# mb_01.net
KiCad netlist of a schematic drawn in EAGLE
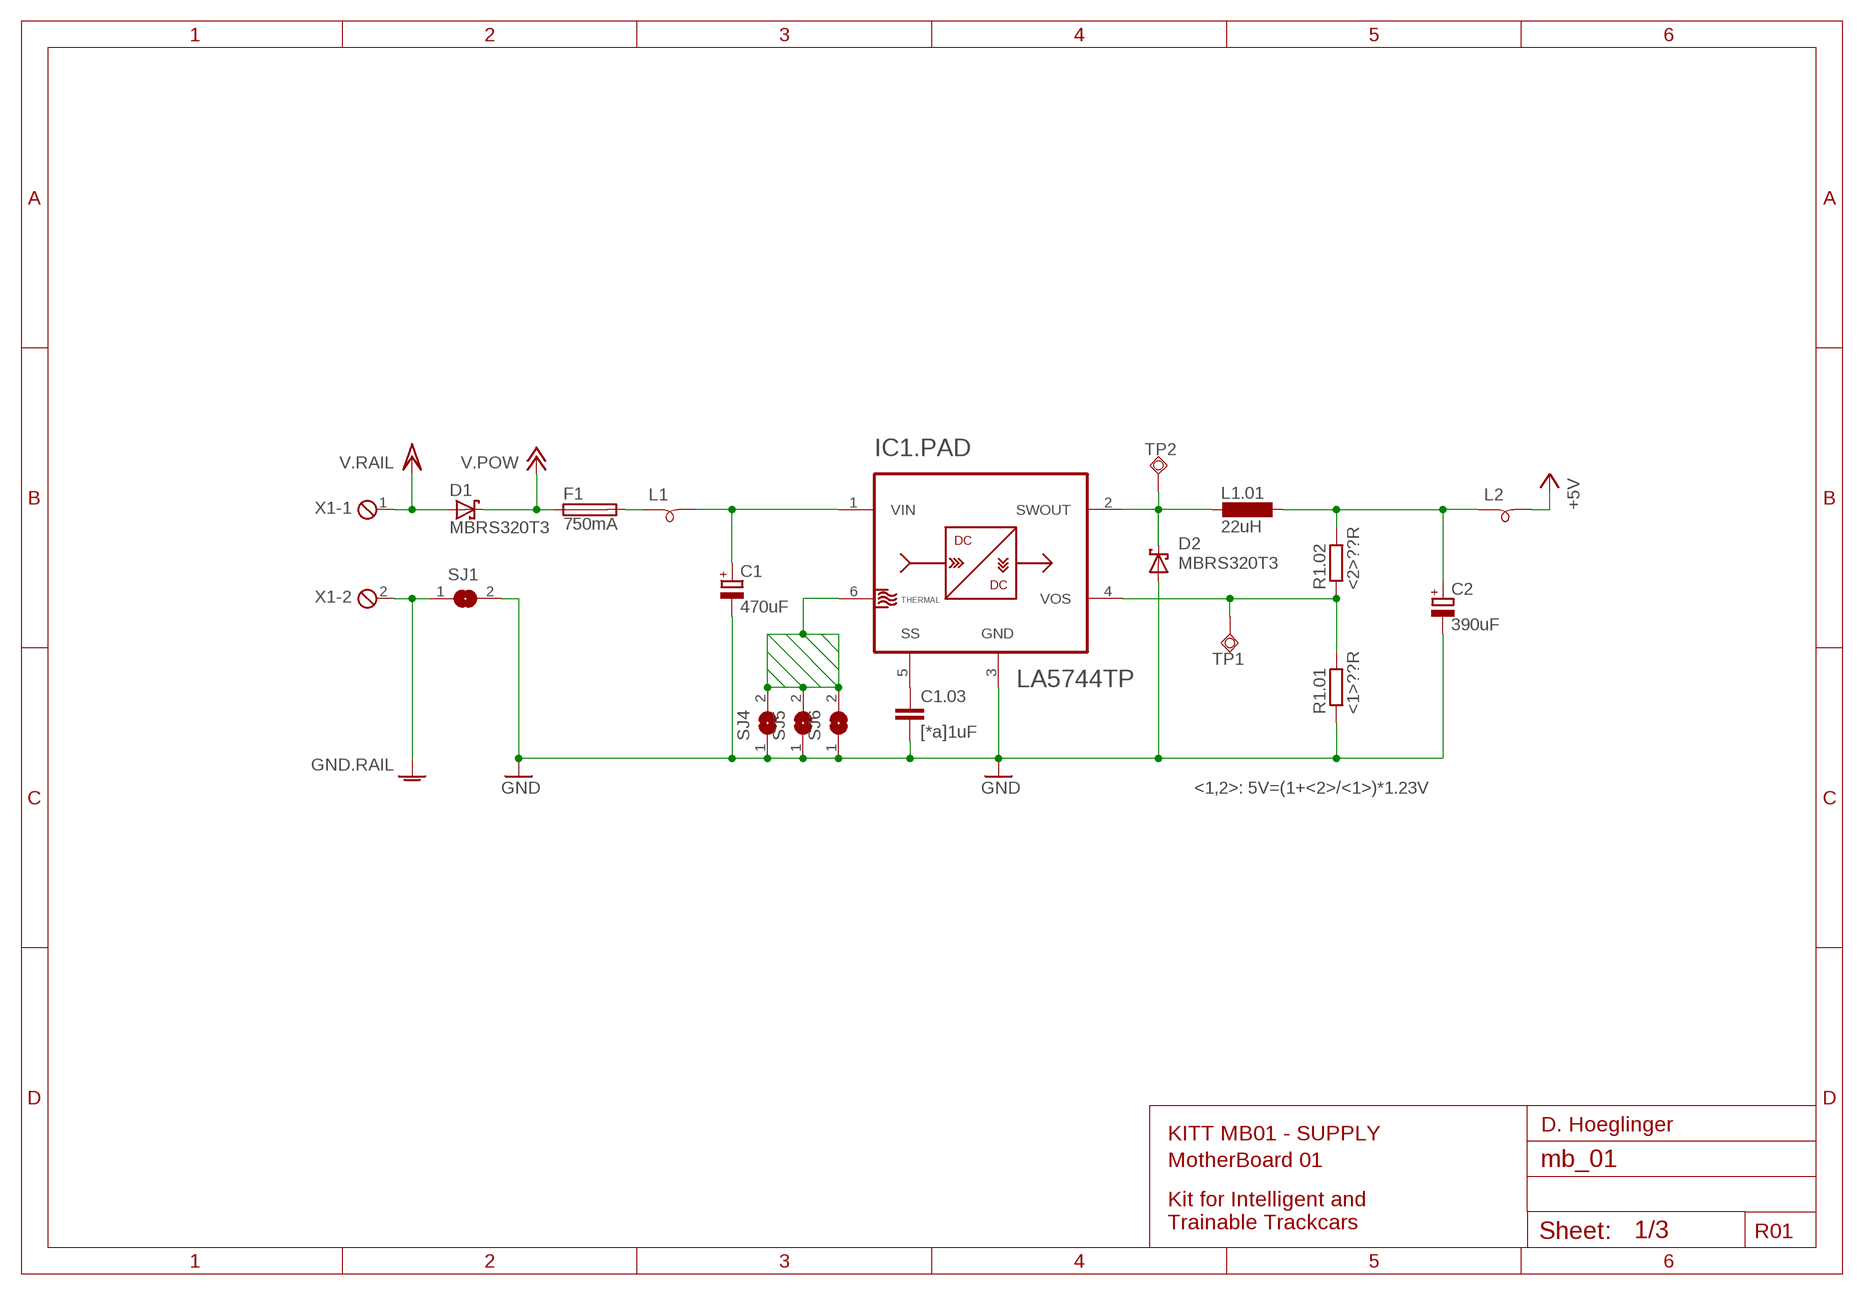
[diagram p0: schematic, sheet 1]
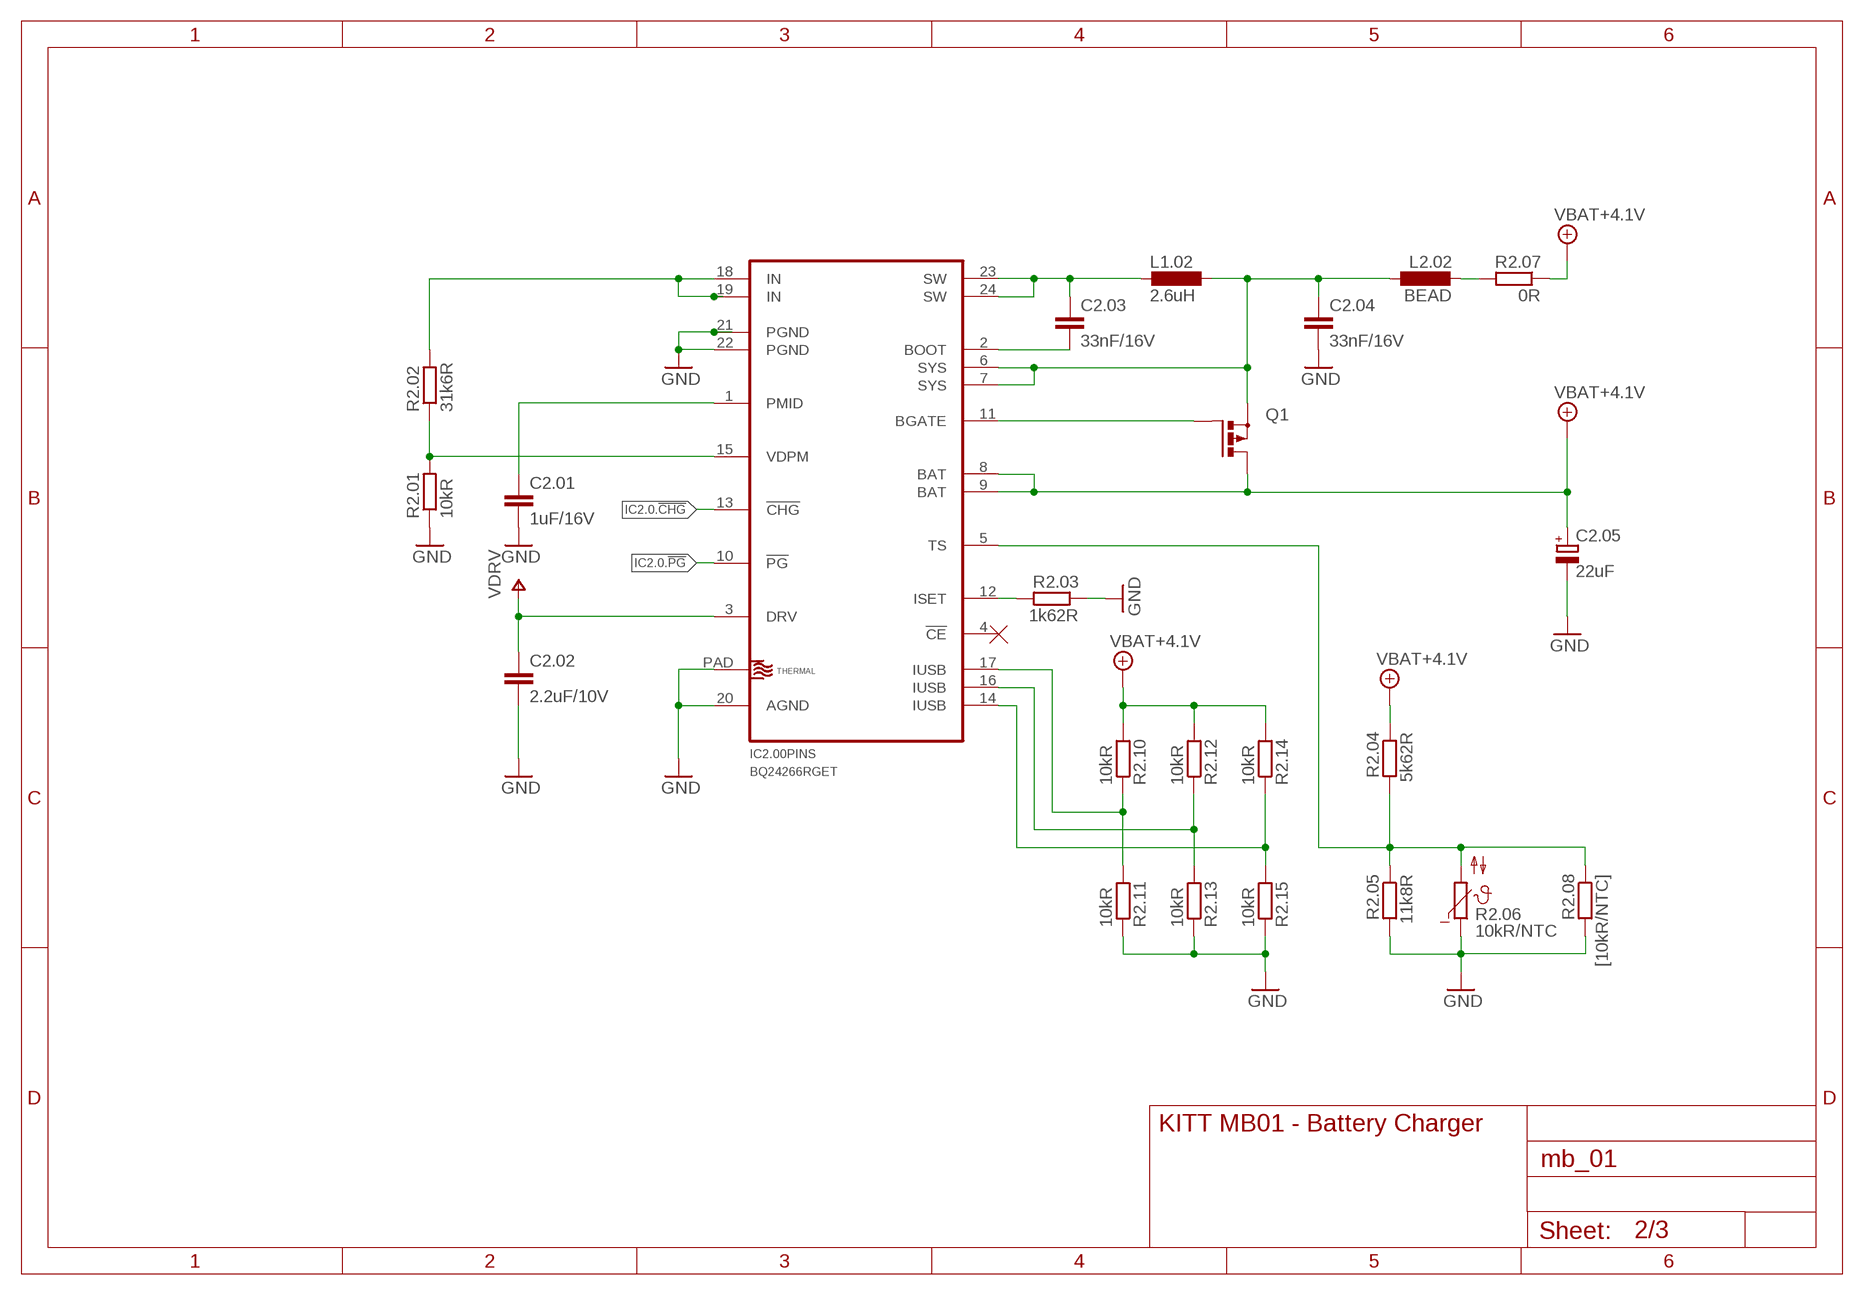
[diagram p1: schematic, sheet 2]
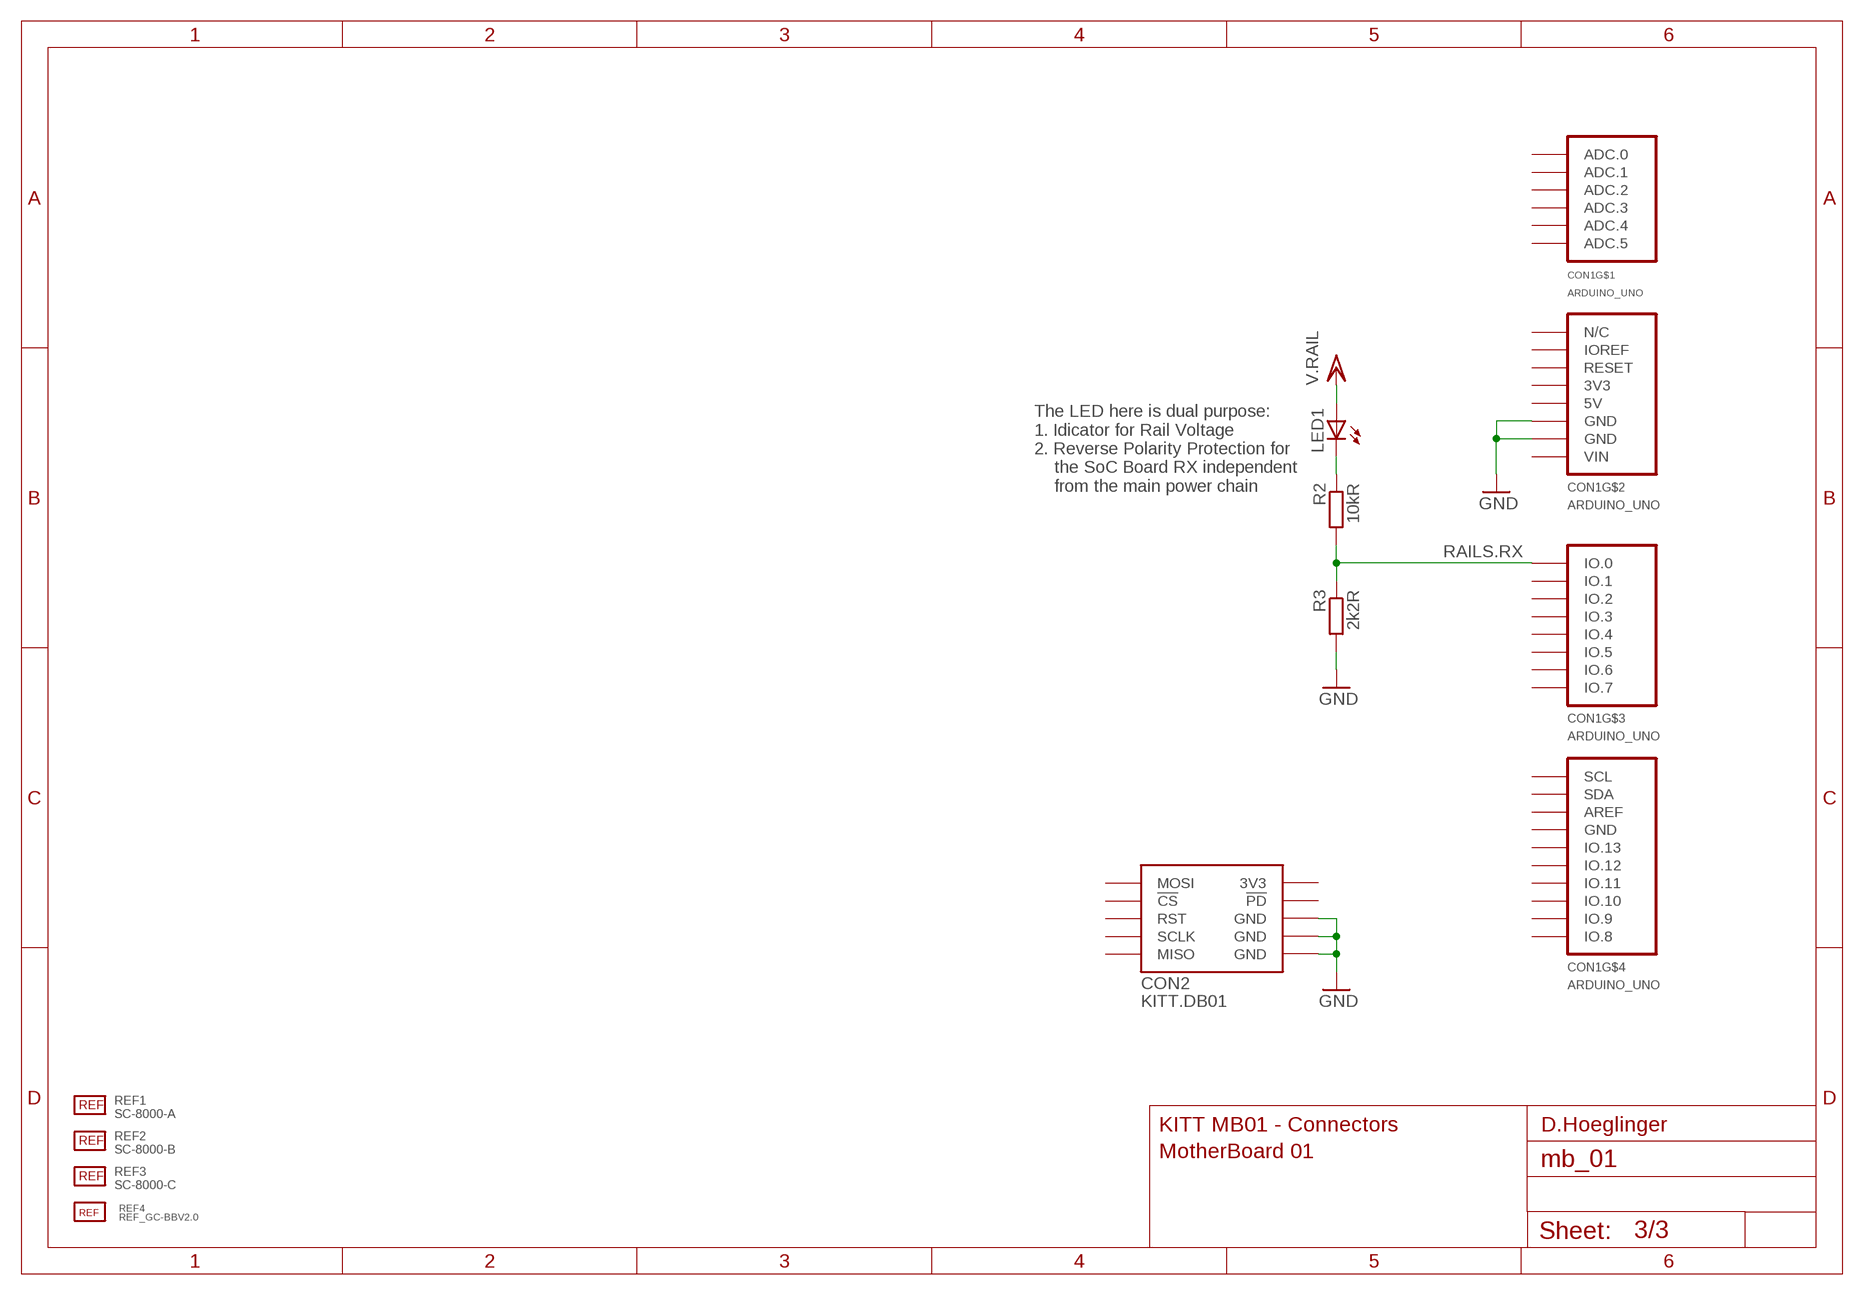
[diagram p2: schematic, sheet 3]

(export (version "E")
  (design (tool "Eeschema 10.0.6"))
  (components
    (comp (ref "CON1")
      (value "ARDUINO_UNO")
      (footprint "eagle-import:AU_PINS")
      (libsource (lib "eagle-import") (part "ARDUINO_UNO"))
    )
    (comp (ref "CON2")
      (value "KITT.DB01")
      (footprint "eagle-import:KITT_DB01")
      (libsource (lib "eagle-import") (part "KITT.DB01"))
    )
    (comp (ref "LED1")
      (value "LG_T679-E1F1-1")
      (footprint "eagle-import:PLCC2")
      (libsource (lib "eagle-import") (part "_T679-?-1E1F1LG"))
    )
    (comp (ref "R2")
      (value "10kR")
      (footprint "eagle-import:M0805")
      (libsource (lib "eagle-import") (part "R-EU_M0805"))
    )
    (comp (ref "R3")
      (value "2k2R")
      (footprint "eagle-import:M0805")
      (libsource (lib "eagle-import") (part "R-EU_M0805"))
    )
    (comp (ref "REF1")
      (value "SC-8000-A")
      (footprint "eagle-import:SC-8000-A")
      (libsource (lib "eagle-import") (part "SC-8000-A"))
    )
    (comp (ref "REF2")
      (value "SC-8000-B")
      (footprint "eagle-import:SC-8000-B")
      (libsource (lib "eagle-import") (part "SC-8000-B"))
    )
    (comp (ref "REF3")
      (value "SC-8000-C")
      (footprint "eagle-import:SC-8000-C")
      (libsource (lib "eagle-import") (part "SC-8000-C"))
    )
    (comp (ref "REF4")
      (value "REF_GC-BBV2.0")
      (footprint "eagle-import:REF_GHOSTCAR")
      (libsource (lib "eagle-import") (part "REF_GC-BBV2.0"))
    )
    (comp (ref "C1")
      (value "470uF")
      (footprint "eagle-import:SMC_P")
      (libsource (lib "eagle-import") (part "CPOL-EUSMCP"))
    )
    (comp (ref "C1.03")
      (value "[*a]1uF")
      (footprint "eagle-import:C0805K")
      (libsource (lib "eagle-import") (part "C-EUC0805K"))
    )
    (comp (ref "C2")
      (value "390uF")
      (footprint "eagle-import:SMC_P")
      (libsource (lib "eagle-import") (part "CPOL-EUSMCP"))
    )
    (comp (ref "D1")
      (value "MBRS320T3")
      (footprint "eagle-import:SMC")
      (libsource (lib "eagle-import") (part "MBRS30T32"))
    )
    (comp (ref "D2")
      (value "MBRS320T3")
      (footprint "eagle-import:SMC")
      (libsource (lib "eagle-import") (part "MBRS30T32"))
    )
    (comp (ref "F1")
      (value "750mA")
      (footprint "eagle-import:MF-SMDF050")
      (libsource (lib "eagle-import") (part "MF-SMDF050"))
    )
    (comp (ref "IC1")
      (value "LA5744TP")
      (footprint "eagle-import:TP-HPA")
      (libsource (lib "eagle-import") (part "LA5744TP"))
    )
    (comp (ref "L1")
      (value "SM-B5")
      (footprint "eagle-import:SM-B5")
      (libsource (lib "eagle-import") (part "SM-B5"))
    )
    (comp (ref "L1.01")
      (value "22uH")
      (footprint "eagle-import:POWER-CHOKE_WE-TPC")
      (libsource (lib "eagle-import") (part "L-EUWE-TPC"))
    )
    (comp (ref "L2")
      (value "SM-B5")
      (footprint "eagle-import:SM-B5")
      (libsource (lib "eagle-import") (part "SM-B5"))
    )
    (comp (ref "R1.01")
      (value "<1>??R")
      (footprint "eagle-import:R0805")
      (libsource (lib "eagle-import") (part "R-EU_R0805"))
    )
    (comp (ref "R1.02")
      (value "<2>??R")
      (footprint "eagle-import:R0805")
      (libsource (lib "eagle-import") (part "R-EU_R0805"))
    )
    (comp (ref "SJ1") (value "SJ") (footprint "eagle-import:SJ") (libsource (lib "eagle-import") (part "SJ")))
    (comp (ref "SJ4") (value "SJ") (footprint "eagle-import:SJ") (libsource (lib "eagle-import") (part "SJ")))
    (comp (ref "SJ5") (value "SJ") (footprint "eagle-import:SJ") (libsource (lib "eagle-import") (part "SJ")))
    (comp (ref "SJ6") (value "SJ") (footprint "eagle-import:SJ") (libsource (lib "eagle-import") (part "SJ")))
    (comp (ref "TP1")
      (value "TPSQTP19SQ")
      (footprint "eagle-import:TP19SQ")
      (libsource (lib "eagle-import") (part "TPSQTP19SQ"))
    )
    (comp (ref "TP2")
      (value "TPSQTP19SQ")
      (footprint "eagle-import:TP19SQ")
      (libsource (lib "eagle-import") (part "TPSQTP19SQ"))
    )
    (comp (ref "X1")
      (value "MPT2")
      (footprint "eagle-import:2POL254")
      (libsource (lib "eagle-import") (part "MPT2"))
    )
    (comp (ref "C2.01")
      (value "1uF/16V")
      (footprint "eagle-import:C0805")
      (libsource (lib "eagle-import") (part "C-EUC0805"))
    )
    (comp (ref "C2.02")
      (value "2.2uF/10V")
      (footprint "eagle-import:C0805")
      (libsource (lib "eagle-import") (part "C-EUC0805"))
    )
    (comp (ref "C2.03")
      (value "33nF/16V")
      (footprint "eagle-import:C0603")
      (libsource (lib "eagle-import") (part "C-EUC0603"))
    )
    (comp (ref "C2.04")
      (value "33nF/16V")
      (footprint "eagle-import:C0805")
      (libsource (lib "eagle-import") (part "C-EUC0805"))
    )
    (comp (ref "C2.05")
      (value "22uF")
      (footprint "eagle-import:A_3216-18R")
      (libsource (lib "eagle-import") (part "CPOL-EUA/3216-18R"))
    )
    (comp (ref "IC2.00")
      (value "BQ24266RGET")
      (footprint "eagle-import:VQFN-24")
      (libsource (lib "eagle-import") (part "BQ24266RGET"))
    )
    (comp (ref "L1.02")
      (value "2.6uH")
      (footprint "eagle-import:POWER-CHOKE_WE-TPC")
      (libsource (lib "eagle-import") (part "L-EUWE-TPC"))
    )
    (comp (ref "L2.02")
      (value "BEAD")
      (footprint "eagle-import:L2012C")
      (libsource (lib "eagle-import") (part "L-EUL2012C"))
    )
    (comp (ref "Q1")
      (value "P-MOSFET-SO8")
      (footprint "eagle-import:SO-08")
      (libsource (lib "eagle-import") (part "P-MOSFET-SO8"))
    )
    (comp (ref "R2.01")
      (value "10kR")
      (footprint "eagle-import:R0402")
      (libsource (lib "eagle-import") (part "R-EU_R0402"))
    )
    (comp (ref "R2.02")
      (value "31k6R")
      (footprint "eagle-import:R0402")
      (libsource (lib "eagle-import") (part "R-EU_R0402"))
    )
    (comp (ref "R2.03")
      (value "1k62R")
      (footprint "eagle-import:R0402")
      (libsource (lib "eagle-import") (part "R-EU_R0402"))
    )
    (comp (ref "R2.04")
      (value "5k62R")
      (footprint "eagle-import:R0402")
      (libsource (lib "eagle-import") (part "R-EU_R0402"))
    )
    (comp (ref "R2.05")
      (value "11k8R")
      (footprint "eagle-import:R0402")
      (libsource (lib "eagle-import") (part "R-EU_R0402"))
    )
    (comp (ref "R2.06")
      (value "10kR/NTC")
      (footprint "eagle-import:P642")
      (libsource (lib "eagle-import") (part "V642"))
    )
    (comp (ref "R2.07")
      (value "0R")
      (footprint "eagle-import:R0402")
      (libsource (lib "eagle-import") (part "R-EU_R0402"))
    )
    (comp (ref "R2.08")
      (value "[10kR/NTC]")
      (footprint "eagle-import:R0402")
      (libsource (lib "eagle-import") (part "R-EU_R0402"))
    )
    (comp (ref "R2.10")
      (value "10kR")
      (footprint "eagle-import:R0402")
      (libsource (lib "eagle-import") (part "R-EU_R0402"))
    )
    (comp (ref "R2.11")
      (value "10kR")
      (footprint "eagle-import:R0402")
      (libsource (lib "eagle-import") (part "R-EU_R0402"))
    )
    (comp (ref "R2.12")
      (value "10kR")
      (footprint "eagle-import:R0402")
      (libsource (lib "eagle-import") (part "R-EU_R0402"))
    )
    (comp (ref "R2.13")
      (value "10kR")
      (footprint "eagle-import:R0402")
      (libsource (lib "eagle-import") (part "R-EU_R0402"))
    )
    (comp (ref "R2.14")
      (value "10kR")
      (footprint "eagle-import:R0402")
      (libsource (lib "eagle-import") (part "R-EU_R0402"))
    )
    (comp (ref "R2.15")
      (value "10kR")
      (footprint "eagle-import:R0402")
      (libsource (lib "eagle-import") (part "R-EU_R0402"))
    )
  )
  (nets
    (net (code "1") (name "+4.1V") (class "Default")
      (node (ref "C2.05") (pin "+") (pinfunction "+_+") (pintype "passive"))
      (node (ref "IC2.00") (pin "8") (pinfunction "BAT_8") (pintype "bidirectional"))
      (node (ref "IC2.00") (pin "9") (pinfunction "BAT_9") (pintype "bidirectional"))
      (node (ref "Q1") (pin "5") (pinfunction "D_5") (pintype "passive"))
      (node (ref "Q1") (pin "6") (pinfunction "D_6") (pintype "passive"))
      (node (ref "Q1") (pin "7") (pinfunction "D_7") (pintype "passive"))
      (node (ref "Q1") (pin "8") (pinfunction "D_8") (pintype "passive"))
      (node (ref "R2.04") (pin "1") (pinfunction "1_1") (pintype "passive"))
      (node (ref "R2.07") (pin "1") (pinfunction "1_1") (pintype "passive"))
      (node (ref "R2.10") (pin "2") (pinfunction "2_2") (pintype "passive"))
      (node (ref "R2.12") (pin "2") (pinfunction "2_2") (pintype "passive"))
      (node (ref "R2.14") (pin "2") (pinfunction "2_2") (pintype "passive"))
    )
    (net (code "2") (name "+5V") (class "Default")
      (node (ref "L2") (pin "2") (pinfunction "2_2") (pintype "passive"))
    )
    (net (code "3") (name "GND") (class "Default")
      (node (ref "C1") (pin "-") (pinfunction "-_-") (pintype "passive"))
      (node (ref "C1.03") (pin "2") (pinfunction "2_2") (pintype "passive"))
      (node (ref "C2") (pin "-") (pinfunction "-_-") (pintype "passive"))
      (node (ref "C2.01") (pin "2") (pinfunction "2_2") (pintype "passive"))
      (node (ref "C2.02") (pin "2") (pinfunction "2_2") (pintype "passive"))
      (node (ref "C2.04") (pin "2") (pinfunction "2_2") (pintype "passive"))
      (node (ref "C2.05") (pin "-") (pinfunction "-_-") (pintype "passive"))
      (node (ref "CON1") (pin "GND2") (pinfunction "GND_GND2") (pintype "bidirectional"))
      (node (ref "CON1") (pin "GND3") (pinfunction "GND_GND3") (pintype "bidirectional"))
      (node (ref "CON2") (pin "10") (pinfunction "GND_10") (pintype "bidirectional"))
      (node (ref "CON2") (pin "6") (pinfunction "GND_6") (pintype "bidirectional"))
      (node (ref "CON2") (pin "8") (pinfunction "GND_8") (pintype "bidirectional"))
      (node (ref "D2") (pin "A") (pinfunction "A_A") (pintype "passive"))
      (node (ref "IC1") (pin "3") (pinfunction "GND_3") (pintype "bidirectional"))
      (node (ref "IC2.00") (pin "20") (pinfunction "AGND_20") (pintype "bidirectional"))
      (node (ref "IC2.00") (pin "21") (pinfunction "PGND_21") (pintype "bidirectional"))
      (node (ref "IC2.00") (pin "22") (pinfunction "PGND_22") (pintype "bidirectional"))
      (node (ref "IC2.00") (pin "PAD") (pinfunction "THERMAL_PAD") (pintype "bidirectional"))
      (node (ref "R1.01") (pin "1") (pinfunction "1_1") (pintype "passive"))
      (node (ref "R2.01") (pin "1") (pinfunction "1_1") (pintype "passive"))
      (node (ref "R2.03") (pin "1") (pinfunction "1_1") (pintype "passive"))
      (node (ref "R2.05") (pin "2") (pinfunction "2_2") (pintype "passive"))
      (node (ref "R2.06") (pin "1") (pinfunction "1_1") (pintype "passive"))
      (node (ref "R2.08") (pin "2") (pinfunction "2_2") (pintype "passive"))
      (node (ref "R2.11") (pin "1") (pinfunction "1_1") (pintype "passive"))
      (node (ref "R2.13") (pin "1") (pinfunction "1_1") (pintype "passive"))
      (node (ref "R2.15") (pin "1") (pinfunction "1_1") (pintype "passive"))
      (node (ref "R3") (pin "2") (pinfunction "2_2") (pintype "passive"))
      (node (ref "SJ1") (pin "2") (pinfunction "2_2") (pintype "passive"))
      (node (ref "SJ4") (pin "1") (pinfunction "1_1") (pintype "passive"))
      (node (ref "SJ5") (pin "1") (pinfunction "1_1") (pintype "passive"))
      (node (ref "SJ6") (pin "1") (pinfunction "1_1") (pintype "passive"))
    )
    (net (code "4") (name "GND.RAIL") (class "Default")
      (node (ref "SJ1") (pin "1") (pinfunction "1_1") (pintype "passive"))
      (node (ref "X1") (pin "2") (pinfunction "1_2") (pintype "passive"))
    )
    (net (code "5") (name "IC2.0.~{CHG}") (class "Default")
      (node (ref "IC2.00") (pin "13") (pinfunction "~{CHG}_13") (pintype "bidirectional"))
    )
    (net (code "6") (name "IC2.0.~{PG}") (class "Default")
      (node (ref "IC2.00") (pin "10") (pinfunction "~{PG}_10") (pintype "bidirectional"))
    )
    (net (code "7") (name "Net-(C2-Pad+)") (class "Default")
      (node (ref "C2") (pin "+") (pinfunction "+_+") (pintype "passive"))
      (node (ref "L1.01") (pin "1") (pinfunction "1_1") (pintype "passive"))
      (node (ref "L2") (pin "1") (pinfunction "1_1") (pintype "passive"))
      (node (ref "R1.02") (pin "2") (pinfunction "2_2") (pintype "passive"))
    )
    (net (code "8") (name "Net-(C2.03-Pad1)") (class "Default")
      (node (ref "C2.03") (pin "1") (pinfunction "1_1") (pintype "passive"))
      (node (ref "IC2.00") (pin "23") (pinfunction "SW_23") (pintype "bidirectional"))
      (node (ref "IC2.00") (pin "24") (pinfunction "SW_24") (pintype "bidirectional"))
      (node (ref "L1.02") (pin "2") (pinfunction "2_2") (pintype "passive"))
    )
    (net (code "9") (name "Net-(C2.04-Pad1)") (class "Default")
      (node (ref "C2.04") (pin "1") (pinfunction "1_1") (pintype "passive"))
      (node (ref "IC2.00") (pin "6") (pinfunction "SYS_6") (pintype "bidirectional"))
      (node (ref "IC2.00") (pin "7") (pinfunction "SYS_7") (pintype "bidirectional"))
      (node (ref "L1.02") (pin "1") (pinfunction "1_1") (pintype "passive"))
      (node (ref "L2.02") (pin "1") (pinfunction "1_1") (pintype "passive"))
      (node (ref "Q1") (pin "1") (pinfunction "S_1") (pintype "passive"))
      (node (ref "Q1") (pin "2") (pinfunction "S_2") (pintype "passive"))
      (node (ref "Q1") (pin "3") (pinfunction "S_3") (pintype "passive"))
    )
    (net (code "10") (name "Net-(F1-Pad2)") (class "Default")
      (node (ref "F1") (pin "2") (pinfunction "2_2") (pintype "passive"))
      (node (ref "L1") (pin "1") (pinfunction "1_1") (pintype "passive"))
    )
    (net (code "11") (name "Net-(IC1A-SS)") (class "Default")
      (node (ref "C1.03") (pin "1") (pinfunction "1_1") (pintype "passive"))
      (node (ref "IC1") (pin "5") (pinfunction "SS_5") (pintype "bidirectional"))
    )
    (net (code "12") (name "Net-(IC1A-SWOUT)") (class "Default")
      (node (ref "D2") (pin "C") (pinfunction "C_C") (pintype "passive"))
      (node (ref "IC1") (pin "2") (pinfunction "SWOUT_2") (pintype "bidirectional"))
      (node (ref "L1.01") (pin "2") (pinfunction "2_2") (pintype "passive"))
      (node (ref "TP2") (pin "TP") (pinfunction "TP_TP") (pintype "input"))
    )
    (net (code "13") (name "Net-(IC1A-VIN)") (class "Default")
      (node (ref "C1") (pin "+") (pinfunction "+_+") (pintype "passive"))
      (node (ref "IC1") (pin "1") (pinfunction "VIN_1") (pintype "bidirectional"))
      (node (ref "L1") (pin "2") (pinfunction "2_2") (pintype "passive"))
    )
    (net (code "14") (name "Net-(IC1A-VOS)") (class "Default")
      (node (ref "IC1") (pin "4") (pinfunction "VOS_4") (pintype "bidirectional"))
      (node (ref "R1.01") (pin "2") (pinfunction "2_2") (pintype "passive"))
      (node (ref "R1.02") (pin "1") (pinfunction "1_1") (pintype "passive"))
      (node (ref "TP1") (pin "TP") (pinfunction "TP_TP") (pintype "input"))
    )
    (net (code "15") (name "Net-(IC1B-THERMAL)") (class "Default")
      (node (ref "IC1") (pin "6") (pinfunction "THERMAL_6") (pintype "bidirectional"))
      (node (ref "SJ4") (pin "2") (pinfunction "2_2") (pintype "passive"))
      (node (ref "SJ5") (pin "2") (pinfunction "2_2") (pintype "passive"))
      (node (ref "SJ6") (pin "2") (pinfunction "2_2") (pintype "passive"))
    )
    (net (code "16") (name "Net-(IC2.00B-BGATE)") (class "Default")
      (node (ref "IC2.00") (pin "11") (pinfunction "BGATE_11") (pintype "bidirectional"))
      (node (ref "Q1") (pin "4") (pinfunction "G_4") (pintype "passive"))
    )
    (net (code "17") (name "Net-(IC2.00B-BOOT)") (class "Default")
      (node (ref "C2.03") (pin "2") (pinfunction "2_2") (pintype "passive"))
      (node (ref "IC2.00") (pin "2") (pinfunction "BOOT_2") (pintype "bidirectional"))
    )
    (net (code "18") (name "Net-(IC2.00B-IN-Pad18)") (class "Default")
      (node (ref "IC2.00") (pin "18") (pinfunction "IN_18") (pintype "bidirectional"))
      (node (ref "IC2.00") (pin "19") (pinfunction "IN_19") (pintype "bidirectional"))
      (node (ref "R2.02") (pin "2") (pinfunction "2_2") (pintype "passive"))
    )
    (net (code "19") (name "Net-(IC2.00B-ISET)") (class "Default")
      (node (ref "IC2.00") (pin "12") (pinfunction "ISET_12") (pintype "bidirectional"))
      (node (ref "R2.03") (pin "2") (pinfunction "2_2") (pintype "passive"))
    )
    (net (code "20") (name "Net-(IC2.00B-IUSB-Pad14)") (class "Default")
      (node (ref "IC2.00") (pin "14") (pinfunction "IUSB_14") (pintype "bidirectional"))
      (node (ref "R2.14") (pin "1") (pinfunction "1_1") (pintype "passive"))
      (node (ref "R2.15") (pin "2") (pinfunction "2_2") (pintype "passive"))
    )
    (net (code "21") (name "Net-(IC2.00B-IUSB-Pad16)") (class "Default")
      (node (ref "IC2.00") (pin "16") (pinfunction "IUSB_16") (pintype "bidirectional"))
      (node (ref "R2.12") (pin "1") (pinfunction "1_1") (pintype "passive"))
      (node (ref "R2.13") (pin "2") (pinfunction "2_2") (pintype "passive"))
    )
    (net (code "22") (name "Net-(IC2.00B-IUSB-Pad17)") (class "Default")
      (node (ref "IC2.00") (pin "17") (pinfunction "IUSB_17") (pintype "bidirectional"))
      (node (ref "R2.10") (pin "1") (pinfunction "1_1") (pintype "passive"))
      (node (ref "R2.11") (pin "2") (pinfunction "2_2") (pintype "passive"))
    )
    (net (code "23") (name "Net-(IC2.00B-PMID)") (class "Default")
      (node (ref "C2.01") (pin "1") (pinfunction "1_1") (pintype "passive"))
      (node (ref "IC2.00") (pin "1") (pinfunction "PMID_1") (pintype "bidirectional"))
    )
    (net (code "24") (name "Net-(IC2.00B-TS)") (class "Default")
      (node (ref "IC2.00") (pin "5") (pinfunction "TS_5") (pintype "bidirectional"))
      (node (ref "R2.04") (pin "2") (pinfunction "2_2") (pintype "passive"))
      (node (ref "R2.05") (pin "1") (pinfunction "1_1") (pintype "passive"))
      (node (ref "R2.06") (pin "2") (pinfunction "2_2") (pintype "passive"))
      (node (ref "R2.08") (pin "1") (pinfunction "1_1") (pintype "passive"))
    )
    (net (code "25") (name "Net-(IC2.00B-VDPM)") (class "Default")
      (node (ref "IC2.00") (pin "15") (pinfunction "VDPM_15") (pintype "bidirectional"))
      (node (ref "R2.01") (pin "2") (pinfunction "2_2") (pintype "passive"))
      (node (ref "R2.02") (pin "1") (pinfunction "1_1") (pintype "passive"))
    )
    (net (code "26") (name "Net-(L2.02-Pad2)") (class "Default")
      (node (ref "L2.02") (pin "2") (pinfunction "2_2") (pintype "passive"))
      (node (ref "R2.07") (pin "2") (pinfunction "2_2") (pintype "passive"))
    )
    (net (code "27") (name "Net-(LED1-PadC)") (class "Default")
      (node (ref "LED1") (pin "C") (pinfunction "C_C") (pintype "passive"))
      (node (ref "R2") (pin "1") (pinfunction "1_1") (pintype "passive"))
    )
    (net (code "28") (name "RAILS.RX") (class "Default")
      (node (ref "CON1") (pin "IO.0") (pinfunction "IO.0_IO.0") (pintype "bidirectional"))
      (node (ref "R2") (pin "2") (pinfunction "2_2") (pintype "passive"))
      (node (ref "R3") (pin "1") (pinfunction "1_1") (pintype "passive"))
    )
    (net (code "29") (name "V.POW") (class "Default")
      (node (ref "D1") (pin "C") (pinfunction "C_C") (pintype "passive"))
      (node (ref "F1") (pin "1") (pinfunction "1_1") (pintype "passive"))
    )
    (net (code "30") (name "VCC{slash}2") (class "Default")
      (node (ref "D1") (pin "A") (pinfunction "A_A") (pintype "passive"))
      (node (ref "LED1") (pin "A") (pinfunction "A_A") (pintype "passive"))
      (node (ref "X1") (pin "1") (pinfunction "1_1") (pintype "passive"))
    )
    (net (code "31") (name "VDRV") (class "Default")
      (node (ref "C2.02") (pin "1") (pinfunction "1_1") (pintype "passive"))
      (node (ref "IC2.00") (pin "3") (pinfunction "DRV_3") (pintype "bidirectional"))
    )
    (net (code "32") (name "unconnected-(CON1-Pad5V)") (class "Default")
      (node (ref "CON1") (pin "5V") (pinfunction "5V_5V") (pintype "bidirectional"))
    )
    (net (code "33") (name "unconnected-(CON1-PadADC.0)") (class "Default")
      (node (ref "CON1") (pin "ADC.0") (pinfunction "ADC.0_ADC.0") (pintype "bidirectional"))
    )
    (net (code "34") (name "unconnected-(CON1-PadADC.1)") (class "Default")
      (node (ref "CON1") (pin "ADC.1") (pinfunction "ADC.1_ADC.1") (pintype "bidirectional"))
    )
    (net (code "35") (name "unconnected-(CON1-PadADC.2)") (class "Default")
      (node (ref "CON1") (pin "ADC.2") (pinfunction "ADC.2_ADC.2") (pintype "bidirectional"))
    )
    (net (code "36") (name "unconnected-(CON1-PadADC.3)") (class "Default")
      (node (ref "CON1") (pin "ADC.3") (pinfunction "ADC.3_ADC.3") (pintype "bidirectional"))
    )
    (net (code "37") (name "unconnected-(CON1-PadADC.4)") (class "Default")
      (node (ref "CON1") (pin "ADC.4") (pinfunction "ADC.4_ADC.4") (pintype "bidirectional"))
    )
    (net (code "38") (name "unconnected-(CON1-PadADC.5)") (class "Default")
      (node (ref "CON1") (pin "ADC.5") (pinfunction "ADC.5_ADC.5") (pintype "bidirectional"))
    )
    (net (code "39") (name "unconnected-(CON1-PadAREF)") (class "Default")
      (node (ref "CON1") (pin "AREF") (pinfunction "AREF_AREF") (pintype "bidirectional"))
    )
    (net (code "40") (name "unconnected-(CON1-PadIO.1)") (class "Default")
      (node (ref "CON1") (pin "IO.1") (pinfunction "IO.1_IO.1") (pintype "bidirectional"))
    )
    (net (code "41") (name "unconnected-(CON1-PadIO.2)") (class "Default")
      (node (ref "CON1") (pin "IO.2") (pinfunction "IO.2_IO.2") (pintype "bidirectional"))
    )
    (net (code "42") (name "unconnected-(CON1-PadIO.3)") (class "Default")
      (node (ref "CON1") (pin "IO.3") (pinfunction "IO.3_IO.3") (pintype "bidirectional"))
    )
    (net (code "43") (name "unconnected-(CON1-PadIO.4)") (class "Default")
      (node (ref "CON1") (pin "IO.4") (pinfunction "IO.4_IO.4") (pintype "bidirectional"))
    )
    (net (code "44") (name "unconnected-(CON1-PadIO.5)") (class "Default")
      (node (ref "CON1") (pin "IO.5") (pinfunction "IO.5_IO.5") (pintype "bidirectional"))
    )
    (net (code "45") (name "unconnected-(CON1-PadIO.6)") (class "Default")
      (node (ref "CON1") (pin "IO.6") (pinfunction "IO.6_IO.6") (pintype "bidirectional"))
    )
    (net (code "46") (name "unconnected-(CON1-PadIO.7)") (class "Default")
      (node (ref "CON1") (pin "IO.7") (pinfunction "IO.7_IO.7") (pintype "bidirectional"))
    )
    (net (code "47") (name "unconnected-(CON1-PadIO.8)") (class "Default")
      (node (ref "CON1") (pin "IO.8") (pinfunction "IO.8_IO.8") (pintype "bidirectional"))
    )
    (net (code "48") (name "unconnected-(CON1-PadIO.9)") (class "Default")
      (node (ref "CON1") (pin "IO.9") (pinfunction "IO.9_IO.9") (pintype "bidirectional"))
    )
    (net (code "49") (name "unconnected-(CON1-PadIO.10)") (class "Default")
      (node (ref "CON1") (pin "IO.10") (pinfunction "IO.10_IO.10") (pintype "bidirectional"))
    )
    (net (code "50") (name "unconnected-(CON1-PadIO.11)") (class "Default")
      (node (ref "CON1") (pin "IO.11") (pinfunction "IO.11_IO.11") (pintype "bidirectional"))
    )
    (net (code "51") (name "unconnected-(CON1-PadIO.12)") (class "Default")
      (node (ref "CON1") (pin "IO.12") (pinfunction "IO.12_IO.12") (pintype "bidirectional"))
    )
    (net (code "52") (name "unconnected-(CON1-PadIO.13)") (class "Default")
      (node (ref "CON1") (pin "IO.13") (pinfunction "IO.13_IO.13") (pintype "bidirectional"))
    )
    (net (code "53") (name "unconnected-(CON1-PadN{slash}C)") (class "Default")
      (node (ref "CON1") (pin "N/C") (pinfunction "N/C_N/C") (pintype "bidirectional"))
    )
    (net (code "54") (name "unconnected-(CON1-PadRESET)") (class "Default")
      (node (ref "CON1") (pin "RESET") (pinfunction "RESET_RESET") (pintype "bidirectional"))
    )
    (net (code "55") (name "unconnected-(CON1-PadSCL)") (class "Default")
      (node (ref "CON1") (pin "SCL") (pinfunction "SCL_SCL") (pintype "bidirectional"))
    )
    (net (code "56") (name "unconnected-(CON1-PadSDA)") (class "Default")
      (node (ref "CON1") (pin "SDA") (pinfunction "SDA_SDA") (pintype "bidirectional"))
    )
    (net (code "57") (name "unconnected-(CON1-PadVIN)") (class "Default")
      (node (ref "CON1") (pin "VIN") (pinfunction "VIN_VIN") (pintype "bidirectional"))
    )
    (net (code "58") (name "unconnected-(CON1B-3V3-Pad3.3V)") (class "Default")
      (node (ref "CON1") (pin "3.3V") (pinfunction "3V3_3.3V") (pintype "bidirectional"))
    )
    (net (code "59") (name "unconnected-(CON1B-IOREF-PadI{slash}OREF)") (class "Default")
      (node (ref "CON1") (pin "I/OREF") (pinfunction "IOREF_I/OREF") (pintype "bidirectional"))
    )
    (net (code "60") (name "unconnected-(CON1D-GND-PadGND.1)") (class "Default")
      (node (ref "CON1") (pin "GND.1") (pinfunction "GND_GND.1") (pintype "bidirectional"))
    )
    (net (code "61") (name "unconnected-(CON2-3V3-Pad2)") (class "Default")
      (node (ref "CON2") (pin "2") (pinfunction "3V3_2") (pintype "bidirectional"))
    )
    (net (code "62") (name "unconnected-(CON2-MISO-Pad9)") (class "Default")
      (node (ref "CON2") (pin "9") (pinfunction "MISO_9") (pintype "bidirectional"))
    )
    (net (code "63") (name "unconnected-(CON2-MOSI-Pad1)") (class "Default")
      (node (ref "CON2") (pin "1") (pinfunction "MOSI_1") (pintype "bidirectional"))
    )
    (net (code "64") (name "unconnected-(CON2-RST-Pad5)") (class "Default")
      (node (ref "CON2") (pin "5") (pinfunction "RST_5") (pintype "bidirectional"))
    )
    (net (code "65") (name "unconnected-(CON2-SCLK-Pad7)") (class "Default")
      (node (ref "CON2") (pin "7") (pinfunction "SCLK_7") (pintype "bidirectional"))
    )
    (net (code "66") (name "unconnected-(CON2-~{CS}-Pad3)") (class "Default")
      (node (ref "CON2") (pin "3") (pinfunction "~{CS}_3") (pintype "bidirectional"))
    )
    (net (code "67") (name "unconnected-(CON2-~{PD}-Pad4)") (class "Default")
      (node (ref "CON2") (pin "4") (pinfunction "~{PD}_4") (pintype "bidirectional"))
    )
    (net (code "68") (name "unconnected-(IC2.00B-~{CE}-Pad4)") (class "Default")
      (node (ref "IC2.00") (pin "4") (pinfunction "~{CE}_4") (pintype "bidirectional"))
    )
  )
)
